# IF.net
KiCad netlist of a schematic drawn in Altium Designer
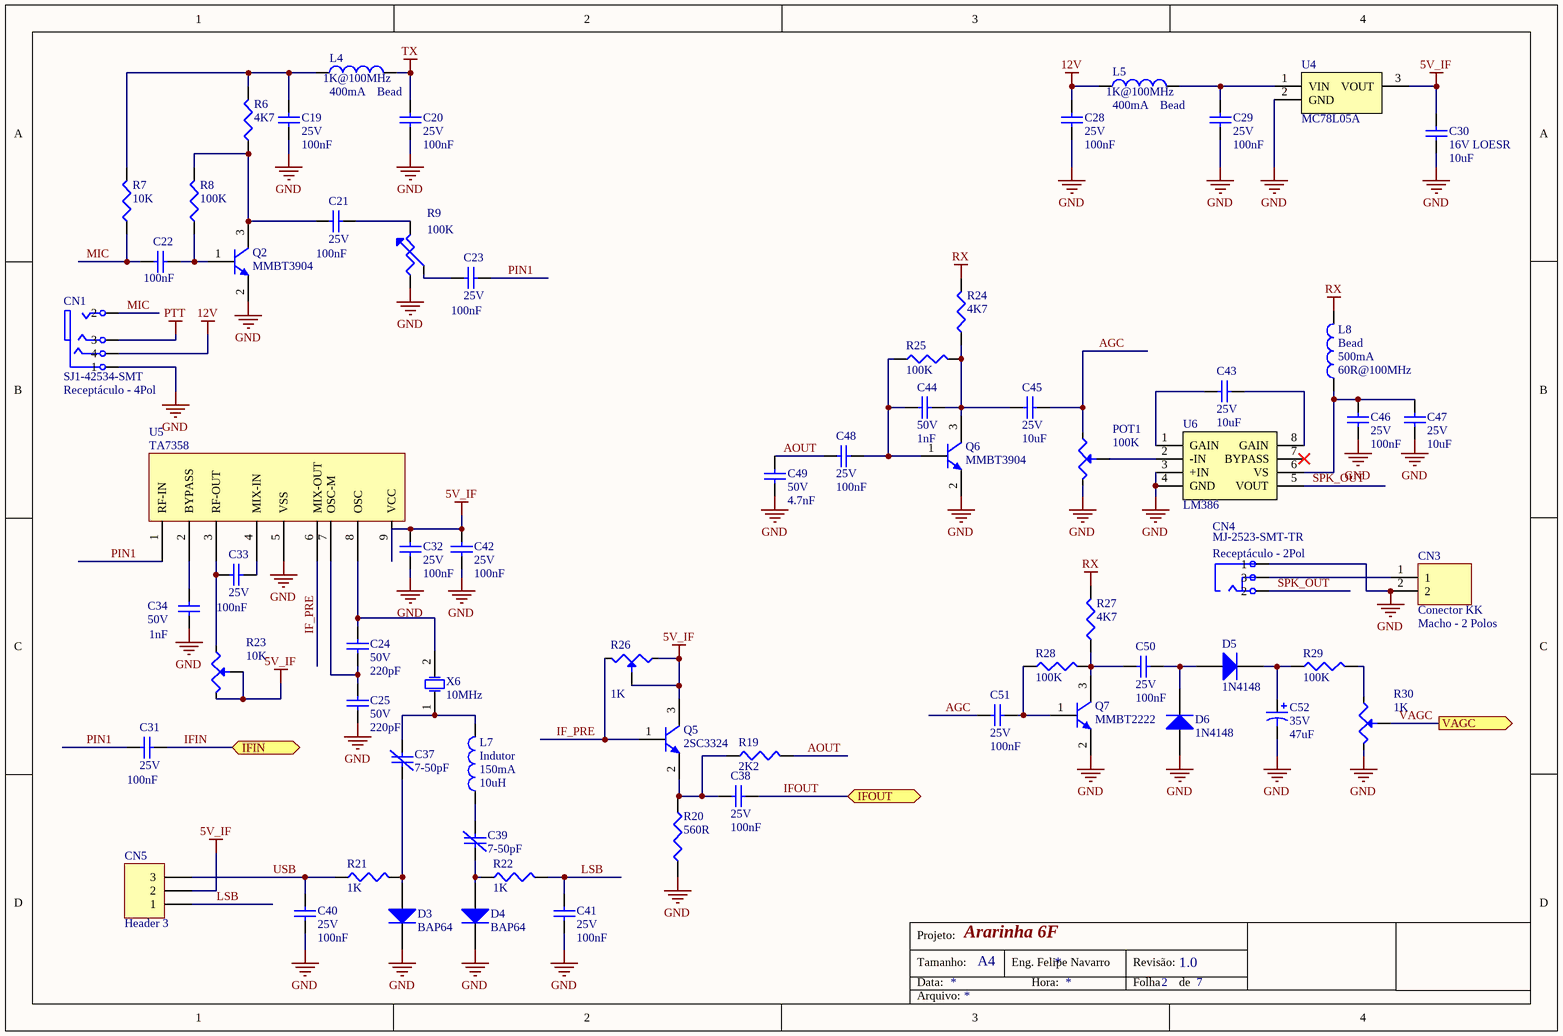
[diagram p0: IF.SchDoc]

(export (version "E")
  (design (tool "Eeschema 10.0.6"))
  (components
    (comp (ref "C19")
      (value "100nF")
      (footprint "CC0603")
      (description "Capacitor (Semiconductor SIM Model)")
      (fields (field (name "TENSÃO") "25V") (field (name "Comment") "Capacitor Cerâmico"))
      (libsource (lib "NavarroCAP") (part "Cap 100nF 25V 0603 X7R"))
    )
    (comp (ref "C20")
      (value "100nF")
      (footprint "CC0603")
      (description "Capacitor (Semiconductor SIM Model)")
      (fields (field (name "TENSÃO") "25V") (field (name "Comment") "Capacitor Cerâmico"))
      (libsource (lib "NavarroCAP") (part "Cap 100nF 25V 0603 X7R"))
    )
    (comp (ref "C21")
      (value "100nF")
      (footprint "CC0603")
      (description "Capacitor (Semiconductor SIM Model)")
      (fields (field (name "TENSÃO") "25V") (field (name "Comment") "Capacitor Cerâmico"))
      (libsource (lib "NavarroCAP") (part "Cap 100nF 25V 0603 X7R"))
    )
    (comp (ref "C22")
      (value "100nF")
      (footprint "CC0603")
      (description "Capacitor (Semiconductor SIM Model)")
      (fields (field (name "Comment") "Capacitor Cerâmico"))
      (libsource (lib "NavarroCAP") (part "Cap 100nF 25V 0603 X7R"))
    )
    (comp (ref "C23")
      (value "100nF")
      (footprint "CC0603")
      (description "Capacitor (Semiconductor SIM Model)")
      (fields (field (name "TENSÃO") "25V") (field (name "Comment") "Capacitor Cerâmico"))
      (libsource (lib "NavarroCAP") (part "Cap 100nF 25V 0603 X7R"))
    )
    (comp (ref "C24")
      (value "220pF")
      (footprint "CC0603")
      (description "Capacitor (Semiconductor SIM Model)")
      (fields (field (name "TENSÃO") "50V") (field (name "Comment") "Capacitor Cerâmico"))
      (libsource (lib "NavarroCAP") (part "Cap 220pF 50V 0603 NP0"))
    )
    (comp (ref "C25")
      (value "220pF")
      (footprint "CC0603")
      (description "Capacitor (Semiconductor SIM Model)")
      (fields (field (name "TENSÃO") "50V") (field (name "Comment") "Capacitor Cerâmico"))
      (libsource (lib "NavarroCAP") (part "Cap 220pF 50V 0603 NP0"))
    )
    (comp (ref "C28")
      (value "100nF")
      (footprint "CC0603")
      (description "Capacitor (Semiconductor SIM Model)")
      (fields (field (name "TENSÃO") "25V") (field (name "Comment") "Capacitor Cerâmico"))
      (libsource (lib "NavarroCAP") (part "Cap 100nF 25V 0603 X7R"))
    )
    (comp (ref "C29")
      (value "100nF")
      (footprint "CC0603")
      (description "Capacitor (Semiconductor SIM Model)")
      (fields (field (name "TENSÃO") "25V") (field (name "Comment") "Capacitor Cerâmico"))
      (libsource (lib "NavarroCAP") (part "Cap 100nF 25V 0603 X7R"))
    )
    (comp (ref "C30")
      (value "10uF")
      (footprint "CC0805")
      (description "Capacitor (Semiconductor SIM Model)")
      (fields (field (name "TENSÃO") "16V LOESR") (field (name "Comment") "Capacitor Cerâmico"))
      (libsource (lib "NavarroCAP") (part "Cap 10uF 16V 0805 X6S LOESR"))
    )
    (comp (ref "C31")
      (value "100nF")
      (footprint "CC0603")
      (description "Capacitor (Semiconductor SIM Model)")
      (fields (field (name "TENSÃO") "25V") (field (name "Comment") "Capacitor Cerâmico"))
      (libsource (lib "NavarroCAP") (part "Cap 100nF 25V 0603 X7R"))
    )
    (comp (ref "C32")
      (value "100nF")
      (footprint "CC0603")
      (description "Capacitor (Semiconductor SIM Model)")
      (fields (field (name "TENSÃO") "25V") (field (name "Comment") "Capacitor Cerâmico"))
      (libsource (lib "NavarroCAP") (part "Cap 100nF 25V 0603 X7R"))
    )
    (comp (ref "C33")
      (value "100nF")
      (footprint "CC0603")
      (description "Capacitor (Semiconductor SIM Model)")
      (fields (field (name "TENSÃO") "25V") (field (name "Comment") "Capacitor Cerâmico"))
      (libsource (lib "NavarroCAP") (part "Cap 100nF 25V 0603 X7R"))
    )
    (comp (ref "C34")
      (value "1nF")
      (footprint "CC0603")
      (description "Capacitor (Semiconductor SIM Model)")
      (fields (field (name "TENSÃO") "50V") (field (name "Comment") "Capacitor Cerâmico"))
      (libsource (lib "NavarroCAP") (part "Cap 1nF 50V 0603 NP0"))
    )
    (comp (ref "C37")
      (value "7-50pF")
      (footprint "MURATA TZB4")
      (description "Capacitor (Semiconductor SIM Model)")
      (fields (field (name "Comment") "Trimmer"))
      (libsource (lib "NavarroCAP") (part "Trimmer 7-50pF 50V TZB4-BB"))
    )
    (comp (ref "C38")
      (value "100nF")
      (footprint "CC0603")
      (description "Capacitor (Semiconductor SIM Model)")
      (fields (field (name "TENSÃO") "25V") (field (name "Comment") "Capacitor Cerâmico"))
      (libsource (lib "NavarroCAP") (part "Cap 100nF 25V 0603 X7R"))
    )
    (comp (ref "C39")
      (value "7-50pF")
      (footprint "MURATA TZB4")
      (description "Capacitor (Semiconductor SIM Model)")
      (fields (field (name "Comment") "Trimmer"))
      (libsource (lib "NavarroCAP") (part "Trimmer 7-50pF 50V TZB4-BB"))
    )
    (comp (ref "C40")
      (value "100nF")
      (footprint "CC0603")
      (description "Capacitor (Semiconductor SIM Model)")
      (fields (field (name "TENSÃO") "25V") (field (name "Comment") "Capacitor Cerâmico"))
      (libsource (lib "NavarroCAP") (part "Cap 100nF 25V 0603 X7R"))
    )
    (comp (ref "C41")
      (value "100nF")
      (footprint "CC0603")
      (description "Capacitor (Semiconductor SIM Model)")
      (fields (field (name "TENSÃO") "25V") (field (name "Comment") "Capacitor Cerâmico"))
      (libsource (lib "NavarroCAP") (part "Cap 100nF 25V 0603 X7R"))
    )
    (comp (ref "C42")
      (value "100nF")
      (footprint "CC0603")
      (description "Capacitor (Semiconductor SIM Model)")
      (fields (field (name "TENSÃO") "25V") (field (name "Comment") "Capacitor Cerâmico"))
      (libsource (lib "NavarroCAP") (part "Cap 100nF 25V 0603 X7R"))
    )
    (comp (ref "C43")
      (value "10uF")
      (footprint "CC0805")
      (description "Capacitor (Semiconductor SIM Model)")
      (fields (field (name "TENSÃO") "25V") (field (name "Comment") "Capacitor Cerâmico"))
      (libsource (lib "NavarroCAP") (part "Cap 10uF 25V 0805 X5R"))
    )
    (comp (ref "C44")
      (value "1nF")
      (footprint "CC0603")
      (description "Capacitor (Semiconductor SIM Model)")
      (fields (field (name "TENSÃO") "50V") (field (name "Comment") "Capacitor Cerâmico"))
      (libsource (lib "NavarroCAP") (part "Cap 1nF 50V 0603 NP0"))
    )
    (comp (ref "C45")
      (value "10uF")
      (footprint "CC0805")
      (description "Capacitor (Semiconductor SIM Model)")
      (fields (field (name "TENSÃO") "25V") (field (name "Comment") "Capacitor Cerâmico"))
      (libsource (lib "NavarroCAP") (part "Cap 10uF 25V 0805 X5R"))
    )
    (comp (ref "C46")
      (value "100nF")
      (footprint "CC0603")
      (description "Capacitor (Semiconductor SIM Model)")
      (fields (field (name "TENSÃO") "25V") (field (name "Comment") "Capacitor Cerâmico"))
      (libsource (lib "NavarroCAP") (part "Cap 100nF 25V 0603 X7R"))
    )
    (comp (ref "C47")
      (value "10uF")
      (footprint "CC0805")
      (description "Capacitor (Semiconductor SIM Model)")
      (fields (field (name "TENSÃO") "25V") (field (name "Comment") "Capacitor Cerâmico"))
      (libsource (lib "NavarroCAP") (part "Cap 10uF 25V 0805 X5R"))
    )
    (comp (ref "C48")
      (value "100nF")
      (footprint "CC0603")
      (description "Capacitor (Semiconductor SIM Model)")
      (fields (field (name "TENSÃO") "25V") (field (name "Comment") "Capacitor Cerâmico"))
      (libsource (lib "NavarroCAP") (part "Cap 100nF 25V 0603 X7R"))
    )
    (comp (ref "C49")
      (value "4.7nF")
      (footprint "CC0603")
      (description "Capacitor (Semiconductor SIM Model)")
      (fields (field (name "TENSÃO") "50V") (field (name "Comment") "Capacitor Cerâmico"))
      (libsource (lib "NavarroCAP") (part "Cap 4.7nF 50V 0603 X7R"))
    )
    (comp (ref "C50")
      (value "100nF")
      (footprint "CC0603")
      (description "Capacitor (Semiconductor SIM Model)")
      (fields (field (name "TENSÃO") "25V") (field (name "Comment") "Capacitor Cerâmico"))
      (libsource (lib "NavarroCAP") (part "Cap 100nF 25V 0603 X7R"))
    )
    (comp (ref "C51")
      (value "100nF")
      (footprint "CC0603")
      (description "Capacitor (Semiconductor SIM Model)")
      (fields (field (name "TENSÃO") "25V") (field (name "Comment") "Capacitor Cerâmico"))
      (libsource (lib "NavarroCAP") (part "Cap 100nF 25V 0603 X7R"))
    )
    (comp (ref "C52")
      (value "47uF")
      (footprint "CPOLRAD5X11")
      (description "Polarized Capacitor (Radial)")
      (fields (field (name "TENSÃO") "35V") (field (name "Comment") "Capacitor Eletrolítico"))
      (libsource (lib "NavarroCAP") (part "PCap 47uF 35V 5d.x11h."))
    )
    (comp (ref "CN1")
      (value "SJ1-42534-SMT")
      (footprint "CONN_JACK-P2_2.5-4N")
      (description "Jack Socket, SMD Vertical, 4-Conductor Open Circuit")
      (fields (field (name "ALTIUM_VALUE") "Receptáculo - 4Pol"))
      (libsource (lib "NavarroCON") (part "Jack-4Pol"))
    )
    (comp (ref "CN3")
      (value "Conector KK")
      (footprint "CONN HDR2-POL P.100")
      (fields (field (name "ALTIUM_VALUE") "Macho - 2 Polos"))
      (libsource (lib "NavarroCON") (part "KK 2P Macho-V P2.54mm"))
    )
    (comp (ref "CN4")
      (value "MJ-2523-SMT-TR")
      (footprint "MJ-2523-SMT-TR")
      (description "CONN AUDIO JACK MONO 2.5MM SMD")
      (fields (field (name "ALTIUM_VALUE") "Receptáculo - 2Pol"))
      (libsource (lib "NavarroCON") (part "MJ-2523-SMT-TR"))
    )
    (comp (ref "CN5")
      (value "Header 3")
      (footprint "CONN HDR1X3")
      (description "Header, 3-Pin")
      (libsource (lib "NavarroCON") (part "Header 3"))
    )
    (comp (ref "D3")
      (value "BAP64")
      (footprint "SOD523")
      (description "PIN DIODE")
      (libsource (lib "NavarroSEMI") (part "PIN BAP64"))
    )
    (comp (ref "D4")
      (value "BAP64")
      (footprint "SOD523")
      (description "PIN DIODE")
      (libsource (lib "NavarroSEMI") (part "PIN BAP64"))
    )
    (comp (ref "D5")
      (value "1N4148")
      (footprint "SOD-323 Diodo-K2")
      (description "Small Signal Diodes")
      (libsource (lib "NavarroSEMI") (part "DP 75V 150mA SOD-323"))
    )
    (comp (ref "D6")
      (value "1N4148")
      (footprint "SOD-323 Diodo-K2")
      (description "Small Signal Diodes")
      (libsource (lib "NavarroSEMI") (part "DP 75V 150mA SOD-323"))
    )
    (comp (ref "L4")
      (value "Bead")
      (footprint "CC0603")
      (fields (field (name "CORRENTE") "400mA") (field (name "ALTIUM_VALUE") "1K@100MHz"))
      (libsource (lib "NavarroIND") (part "Bd 1K@100MHz 0603 400mA"))
    )
    (comp (ref "L5")
      (value "Bead")
      (footprint "CC0603")
      (fields (field (name "CORRENTE") "400mA") (field (name "ALTIUM_VALUE") "1K@100MHz"))
      (libsource (lib "NavarroIND") (part "Bd 1K@100MHz 0603 400mA"))
    )
    (comp (ref "L7")
      (value "Indutor")
      (footprint "CC0805")
      (description "Inductor")
      (fields (field (name "CORRENTE") "150mA") (field (name "ALTIUM_VALUE") "10uH"))
      (libsource (lib "NavarroIND") (part "Ind 10uH 0805 150mA"))
    )
    (comp (ref "L8")
      (value "Bead")
      (footprint "CC0603")
      (fields (field (name "CORRENTE") "500mA") (field (name "ALTIUM_VALUE") "60R@100MHz"))
      (libsource (lib "NavarroIND") (part "Bd 60R@100MHz 0603 500mA"))
    )
    (comp (ref "POT1")
      (value "100K")
      (footprint "POT - PTV09")
      (description "Potenciometro")
      (fields (field (name "Comment") "Potenciômetro"))
      (libsource (lib "NavarroRES") (part "POT 100k Audio"))
    )
    (comp (ref "Q2")
      (value "MMBT3904")
      (footprint "SOT-23-3N")
      (description "NPN General Purpose Amplifier")
      (libsource (lib "NavarroSEMI") (part "TRS MMBT3904 40V 200mA SOT-23-3N"))
    )
    (comp (ref "Q5")
      (value "2SC3324")
      (footprint "SOT-23-3N")
      (description "NPN General Purpose Amplifier")
      (libsource (lib "NavarroSEMI") (part "TRS 2SC3324 120V 100mA SOT-23-3"))
    )
    (comp (ref "Q6")
      (value "MMBT3904")
      (footprint "SOT-23-3N")
      (description "NPN General Purpose Amplifier")
      (libsource (lib "NavarroSEMI") (part "TRS MMBT3904 40V 200mA SOT-23-3N"))
    )
    (comp (ref "Q7")
      (value "MMBT2222")
      (footprint "SOT-23-3N")
      (description "NPN General Purpose Amplifier")
      (libsource (lib "NavarroSEMI") (part "TRS MMBT2222 40V 200mA SOT-23-3N"))
    )
    (comp (ref "R6")
      (value "4K7")
      (footprint "CC0603")
      (description "Resistor")
      (libsource (lib "NavarroRES") (part "Res 4K7 1% 0603 1/10W"))
    )
    (comp (ref "R7")
      (value "10K")
      (footprint "CC0603")
      (description "Resistor")
      (libsource (lib "NavarroRES") (part "Res 10K 1% 0603 1/10W"))
    )
    (comp (ref "R8")
      (value "100K")
      (footprint "CC0603")
      (description "Resistor")
      (libsource (lib "NavarroRES") (part "Res 100K 1% 0603 1/10W"))
    )
    (comp (ref "R9")
      (value "100K")
      (footprint "POT")
      (description "Trimmer")
      (fields (field (name "Comment") "Potenciômetro"))
      (libsource (lib "NavarroRES") (part "Res Trim"))
    )
    (comp (ref "R19")
      (value "2K2")
      (footprint "CC0603")
      (description "Resistor")
      (libsource (lib "NavarroRES") (part "Res 2K2 5% 0603 1/10W"))
    )
    (comp (ref "R20")
      (value "560R")
      (footprint "CC0603")
      (description "Resistor")
      (libsource (lib "NavarroRES") (part "Res 560R 1% 0603 1/10w"))
    )
    (comp (ref "R21")
      (value "1K")
      (footprint "CC0603")
      (description "Resistor")
      (libsource (lib "NavarroRES") (part "Res 1K 1% 0603 1/10W"))
    )
    (comp (ref "R22")
      (value "1K")
      (footprint "CC0603")
      (description "Resistor")
      (libsource (lib "NavarroRES") (part "Res 1K 1% 0603 1/10W"))
    )
    (comp (ref "R23")
      (value "10K")
      (footprint "POT")
      (description "Potenciometro")
      (fields (field (name "Comment") "Potenciômetro"))
      (libsource (lib "NavarroRES") (part "Res Pot"))
    )
    (comp (ref "R24")
      (value "4K7")
      (footprint "CC0603")
      (description "Resistor")
      (libsource (lib "NavarroRES") (part "Res 4K7 1% 0603 1/10W"))
    )
    (comp (ref "R25")
      (value "100K")
      (footprint "CC0603")
      (description "Resistor")
      (libsource (lib "NavarroRES") (part "Res 100K 1% 0603 1/10W"))
    )
    (comp (ref "R26")
      (value "1K")
      (footprint "POT")
      (description "Potenciometro")
      (fields (field (name "Comment") "Potenciômetro"))
      (libsource (lib "NavarroRES") (part "Res Pot"))
    )
    (comp (ref "R27")
      (value "4K7")
      (footprint "CC0603")
      (description "Resistor")
      (libsource (lib "NavarroRES") (part "Res 4K7 1% 0603 1/10W"))
    )
    (comp (ref "R28")
      (value "100K")
      (footprint "CC0603")
      (description "Resistor")
      (libsource (lib "NavarroRES") (part "Res 100K 1% 0603 1/10W"))
    )
    (comp (ref "R29")
      (value "100K")
      (footprint "CC0603")
      (description "Resistor")
      (libsource (lib "NavarroRES") (part "Res 100K 1% 0603 1/10W"))
    )
    (comp (ref "R30")
      (value "1K")
      (footprint "POT")
      (description "Potenciometro")
      (fields (field (name "Comment") "Potenciômetro"))
      (libsource (lib "NavarroRES") (part "Res Pot"))
    )
    (comp (ref "U4")
      (value "MC78L05A")
      (footprint "SOT-89-3N")
      (description "Regulador Linear 5V")
      (libsource (lib "Navarro") (part "MC78L05"))
    )
    (comp (ref "U5")
      (value "TA7358")
      (footprint "SIP9")
      (description "FM FRONT-END")
      (libsource (lib "Navarro") (part "TA7358"))
    )
    (comp (ref "U6")
      (value "LM386")
      (footprint "SOIC-8N")
      (description "IC AMP AUDIO PWR .325W AB 8SOIC")
      (libsource (lib "Navarro") (part "LM386"))
    )
    (comp (ref "X6")
      (value "10MHz")
      (footprint "HC/49US")
      (description "Crystal Oscillator")
      (libsource (lib "Navarro") (part "XTAL"))
    )
  )
  (nets
    (net (code "1") (name "/AGC") (class "Default")
      (node (ref "C45") (pin "2") (pinfunction "2_2") (pintype "passive"))
      (node (ref "C51") (pin "1") (pinfunction "1_1") (pintype "passive"))
      (node (ref "POT1") (pin "1") (pinfunction "1_1") (pintype "passive"))
    )
    (net (code "2") (name "/AOUT") (class "Default")
      (node (ref "C48") (pin "1") (pinfunction "1_1") (pintype "passive"))
      (node (ref "C49") (pin "2") (pinfunction "2_2") (pintype "passive"))
      (node (ref "R19") (pin "2") (pinfunction "2_2") (pintype "passive"))
    )
    (net (code "3") (name "/IFIN") (class "Default")
      (node (ref "C31") (pin "1") (pinfunction "1_1") (pintype "passive"))
    )
    (net (code "4") (name "/IFOUT") (class "Default")
      (node (ref "C38") (pin "2") (pinfunction "2_2") (pintype "passive"))
    )
    (net (code "5") (name "/IF_PRE") (class "Default")
      (node (ref "Q5") (pin "1") (pinfunction "B_1") (pintype "passive"))
      (node (ref "R26") (pin "3") (pinfunction "3_3") (pintype "passive"))
      (node (ref "U5") (pin "6") (pinfunction "MIX-OUT_6") (pintype "passive"))
    )
    (net (code "6") (name "/LSB") (class "Default")
      (node (ref "C41") (pin "1") (pinfunction "1_1") (pintype "passive"))
      (node (ref "CN5") (pin "1") (pinfunction "1_1") (pintype "passive"))
      (node (ref "R22") (pin "2") (pinfunction "2_2") (pintype "passive"))
    )
    (net (code "7") (name "/MIC") (class "Default")
      (node (ref "C22") (pin "2") (pinfunction "2_2") (pintype "passive"))
      (node (ref "CN1") (pin "2") (pinfunction "2_2") (pintype "power_in"))
      (node (ref "R7") (pin "1") (pinfunction "1_1") (pintype "passive"))
    )
    (net (code "8") (name "/PIN1") (class "Default")
      (node (ref "C23") (pin "1") (pinfunction "1_1") (pintype "passive"))
      (node (ref "C31") (pin "2") (pinfunction "2_2") (pintype "passive"))
      (node (ref "U5") (pin "1") (pinfunction "RF-IN_1") (pintype "passive"))
    )
    (net (code "9") (name "/SPK_OUT") (class "Default")
      (node (ref "CN4") (pin "2") (pinfunction "2_2") (pintype "power_in"))
      (node (ref "U6") (pin "5") (pinfunction "VOUT_5") (pintype "passive"))
    )
    (net (code "10") (name "/USB") (class "Default")
      (node (ref "C40") (pin "1") (pinfunction "1_1") (pintype "passive"))
      (node (ref "CN5") (pin "3") (pinfunction "3_3") (pintype "passive"))
      (node (ref "R21") (pin "1") (pinfunction "1_1") (pintype "passive"))
    )
    (net (code "11") (name "/VAGC") (class "Default")
      (node (ref "R30") (pin "2") (pinfunction "TAP_2") (pintype "passive"))
    )
    (net (code "12") (name "5V_IF") (class "Default")
      (node (ref "C30") (pin "2") (pinfunction "2_2") (pintype "passive"))
      (node (ref "C32") (pin "1") (pinfunction "1_1") (pintype "passive"))
      (node (ref "C42") (pin "1") (pinfunction "1_1") (pintype "passive"))
      (node (ref "CN5") (pin "2") (pinfunction "2_2") (pintype "passive"))
      (node (ref "Q5") (pin "3") (pinfunction "C_3") (pintype "passive"))
      (node (ref "R23") (pin "2") (pinfunction "TAP_2") (pintype "passive"))
      (node (ref "R23") (pin "3") (pinfunction "3_3") (pintype "passive"))
      (node (ref "R26") (pin "1") (pinfunction "1_1") (pintype "passive"))
      (node (ref "R26") (pin "2") (pinfunction "TAP_2") (pintype "passive"))
      (node (ref "U4") (pin "3") (pinfunction "VOUT_3") (pintype "power_in"))
      (node (ref "U5") (pin "9") (pinfunction "VCC_9") (pintype "passive"))
    )
    (net (code "13") (name "12V") (class "Default")
      (node (ref "C28") (pin "1") (pinfunction "1_1") (pintype "passive"))
      (node (ref "CN1") (pin "4") (pinfunction "4_4") (pintype "power_in"))
      (node (ref "L5") (pin "1") (pinfunction "1_1") (pintype "passive"))
    )
    (net (code "14") (name "GND") (class "Default")
      (node (ref "C19") (pin "2") (pinfunction "2_2") (pintype "passive"))
      (node (ref "C20") (pin "2") (pinfunction "2_2") (pintype "passive"))
      (node (ref "C25") (pin "1") (pinfunction "1_1") (pintype "passive"))
      (node (ref "C28") (pin "2") (pinfunction "2_2") (pintype "passive"))
      (node (ref "C29") (pin "2") (pinfunction "2_2") (pintype "passive"))
      (node (ref "C30") (pin "1") (pinfunction "1_1") (pintype "passive"))
      (node (ref "C32") (pin "2") (pinfunction "2_2") (pintype "passive"))
      (node (ref "C34") (pin "2") (pinfunction "2_2") (pintype "passive"))
      (node (ref "C40") (pin "2") (pinfunction "2_2") (pintype "passive"))
      (node (ref "C41") (pin "2") (pinfunction "2_2") (pintype "passive"))
      (node (ref "C42") (pin "2") (pinfunction "2_2") (pintype "passive"))
      (node (ref "C46") (pin "2") (pinfunction "2_2") (pintype "passive"))
      (node (ref "C47") (pin "1") (pinfunction "1_1") (pintype "passive"))
      (node (ref "C49") (pin "1") (pinfunction "1_1") (pintype "passive"))
      (node (ref "C52") (pin "2") (pinfunction "2_2") (pintype "passive"))
      (node (ref "CN1") (pin "1") (pinfunction "1_1") (pintype "passive"))
      (node (ref "CN3") (pin "2") (pinfunction "2_2") (pintype "passive"))
      (node (ref "CN4") (pin "1") (pinfunction "1_1") (pintype "passive"))
      (node (ref "D3") (pin "2") (pinfunction "K_2") (pintype "passive"))
      (node (ref "D4") (pin "2") (pinfunction "K_2") (pintype "passive"))
      (node (ref "D6") (pin "1") (pinfunction "A_1") (pintype "passive"))
      (node (ref "POT1") (pin "3") (pinfunction "3_3") (pintype "passive"))
      (node (ref "Q2") (pin "2") (pinfunction "E_2") (pintype "passive"))
      (node (ref "Q6") (pin "2") (pinfunction "E_2") (pintype "passive"))
      (node (ref "Q7") (pin "2") (pinfunction "E_2") (pintype "passive"))
      (node (ref "R20") (pin "1") (pinfunction "1_1") (pintype "passive"))
      (node (ref "R30") (pin "3") (pinfunction "3_3") (pintype "passive"))
      (node (ref "R9") (pin "2") (pinfunction "2_2") (pintype "passive"))
      (node (ref "U4") (pin "2") (pinfunction "GND_2") (pintype "power_in"))
      (node (ref "U5") (pin "5") (pinfunction "VSS_5") (pintype "passive"))
      (node (ref "U6") (pin "3") (pinfunction "+IN_3") (pintype "passive"))
      (node (ref "U6") (pin "4") (pinfunction "GND_4") (pintype "passive"))
    )
    (net (code "15") (name "Net-(C19-Pad1)") (class "Default")
      (node (ref "C19") (pin "1") (pinfunction "1_1") (pintype "passive"))
      (node (ref "L4") (pin "1") (pinfunction "1_1") (pintype "passive"))
      (node (ref "R6") (pin "2") (pinfunction "2_2") (pintype "passive"))
      (node (ref "R7") (pin "2") (pinfunction "2_2") (pintype "passive"))
    )
    (net (code "16") (name "Net-(C21-Pad1)") (class "Default")
      (node (ref "C21") (pin "1") (pinfunction "1_1") (pintype "passive"))
      (node (ref "R9") (pin "1") (pinfunction "1_1") (pintype "passive"))
    )
    (net (code "17") (name "Net-(C39-Pad2)") (class "Default")
      (node (ref "C39") (pin "2") (pinfunction "2_2") (pintype "passive"))
      (node (ref "L7") (pin "1") (pinfunction "1_1") (pintype "passive"))
    )
    (net (code "18") (name "Net-(C43-Pad1)") (class "Default")
      (node (ref "C43") (pin "1") (pinfunction "1_1") (pintype "passive"))
      (node (ref "U6") (pin "1") (pinfunction "GAIN_1") (pintype "passive"))
    )
    (net (code "19") (name "Net-(C43-Pad2)") (class "Default")
      (node (ref "C43") (pin "2") (pinfunction "2_2") (pintype "passive"))
      (node (ref "U6") (pin "8") (pinfunction "GAIN_8") (pintype "passive"))
    )
    (net (code "20") (name "Net-(CN3-Pad1)") (class "Default")
      (node (ref "CN3") (pin "1") (pinfunction "1_1") (pintype "passive"))
      (node (ref "CN4") (pin "3") (pinfunction "3_3") (pintype "power_in"))
    )
    (net (code "21") (name "Net-(D3-A)") (class "Default")
      (node (ref "C37") (pin "1") (pinfunction "1_1") (pintype "passive"))
      (node (ref "D3") (pin "1") (pinfunction "A_1") (pintype "passive"))
      (node (ref "R21") (pin "2") (pinfunction "2_2") (pintype "passive"))
    )
    (net (code "22") (name "Net-(D4-A)") (class "Default")
      (node (ref "C39") (pin "1") (pinfunction "1_1") (pintype "passive"))
      (node (ref "D4") (pin "1") (pinfunction "A_1") (pintype "passive"))
      (node (ref "R22") (pin "1") (pinfunction "1_1") (pintype "passive"))
    )
    (net (code "23") (name "Net-(D5-A)") (class "Default")
      (node (ref "C50") (pin "2") (pinfunction "2_2") (pintype "passive"))
      (node (ref "D5") (pin "1") (pinfunction "A_1") (pintype "passive"))
      (node (ref "D6") (pin "2") (pinfunction "K_2") (pintype "passive"))
    )
    (net (code "24") (name "Net-(D5-K)") (class "Default")
      (node (ref "C52") (pin "1") (pinfunction "1_1") (pintype "passive"))
      (node (ref "D5") (pin "2") (pinfunction "K_2") (pintype "passive"))
      (node (ref "R29") (pin "1") (pinfunction "1_1") (pintype "passive"))
    )
    (net (code "25") (name "Net-(POT1-TAP)") (class "Default")
      (node (ref "POT1") (pin "2") (pinfunction "TAP_2") (pintype "passive"))
      (node (ref "U6") (pin "2") (pinfunction "-IN_2") (pintype "passive"))
    )
    (net (code "26") (name "Net-(Q2-B)") (class "Default")
      (node (ref "C22") (pin "1") (pinfunction "1_1") (pintype "passive"))
      (node (ref "Q2") (pin "1") (pinfunction "B_1") (pintype "passive"))
      (node (ref "R8") (pin "1") (pinfunction "1_1") (pintype "passive"))
    )
    (net (code "27") (name "Net-(Q2-C)") (class "Default")
      (node (ref "C21") (pin "2") (pinfunction "2_2") (pintype "passive"))
      (node (ref "Q2") (pin "3") (pinfunction "C_3") (pintype "passive"))
      (node (ref "R6") (pin "1") (pinfunction "1_1") (pintype "passive"))
      (node (ref "R8") (pin "2") (pinfunction "2_2") (pintype "passive"))
    )
    (net (code "28") (name "Net-(Q5-E)") (class "Default")
      (node (ref "C38") (pin "1") (pinfunction "1_1") (pintype "passive"))
      (node (ref "Q5") (pin "2") (pinfunction "E_2") (pintype "passive"))
      (node (ref "R19") (pin "1") (pinfunction "1_1") (pintype "passive"))
      (node (ref "R20") (pin "2") (pinfunction "2_2") (pintype "passive"))
    )
    (net (code "29") (name "Net-(Q6-B)") (class "Default")
      (node (ref "C44") (pin "1") (pinfunction "1_1") (pintype "passive"))
      (node (ref "C48") (pin "2") (pinfunction "2_2") (pintype "passive"))
      (node (ref "Q6") (pin "1") (pinfunction "B_1") (pintype "passive"))
      (node (ref "R25") (pin "1") (pinfunction "1_1") (pintype "passive"))
    )
    (net (code "30") (name "Net-(Q6-C)") (class "Default")
      (node (ref "C44") (pin "2") (pinfunction "2_2") (pintype "passive"))
      (node (ref "C45") (pin "1") (pinfunction "1_1") (pintype "passive"))
      (node (ref "Q6") (pin "3") (pinfunction "C_3") (pintype "passive"))
      (node (ref "R24") (pin "1") (pinfunction "1_1") (pintype "passive"))
      (node (ref "R25") (pin "2") (pinfunction "2_2") (pintype "passive"))
    )
    (net (code "31") (name "Net-(Q7-B)") (class "Default")
      (node (ref "C51") (pin "2") (pinfunction "2_2") (pintype "passive"))
      (node (ref "Q7") (pin "1") (pinfunction "B_1") (pintype "passive"))
      (node (ref "R28") (pin "1") (pinfunction "1_1") (pintype "passive"))
    )
    (net (code "32") (name "Net-(Q7-C)") (class "Default")
      (node (ref "C50") (pin "1") (pinfunction "1_1") (pintype "passive"))
      (node (ref "Q7") (pin "3") (pinfunction "C_3") (pintype "passive"))
      (node (ref "R27") (pin "1") (pinfunction "1_1") (pintype "passive"))
      (node (ref "R28") (pin "2") (pinfunction "2_2") (pintype "passive"))
    )
    (net (code "33") (name "Net-(R9-TAP)") (class "Default")
      (node (ref "C23") (pin "2") (pinfunction "2_2") (pintype "passive"))
      (node (ref "R9") (pin "3") (pinfunction "TAP_3") (pintype "passive"))
    )
    (net (code "34") (name "Net-(R29-Pad2)") (class "Default")
      (node (ref "R29") (pin "2") (pinfunction "2_2") (pintype "passive"))
      (node (ref "R30") (pin "1") (pinfunction "1_1") (pintype "passive"))
    )
    (net (code "35") (name "Net-(U4-VIN)") (class "Default")
      (node (ref "C29") (pin "1") (pinfunction "1_1") (pintype "passive"))
      (node (ref "L5") (pin "2") (pinfunction "2_2") (pintype "passive"))
      (node (ref "U4") (pin "1") (pinfunction "VIN_1") (pintype "power_in"))
    )
    (net (code "36") (name "Net-(U5-BYPASS)") (class "Default")
      (node (ref "C34") (pin "1") (pinfunction "1_1") (pintype "passive"))
      (node (ref "U5") (pin "2") (pinfunction "BYPASS_2") (pintype "passive"))
    )
    (net (code "37") (name "Net-(U5-MIX-IN)") (class "Default")
      (node (ref "C33") (pin "1") (pinfunction "1_1") (pintype "passive"))
      (node (ref "U5") (pin "4") (pinfunction "MIX-IN_4") (pintype "passive"))
    )
    (net (code "38") (name "Net-(U5-OSC)") (class "Default")
      (node (ref "C24") (pin "2") (pinfunction "2_2") (pintype "passive"))
      (node (ref "U5") (pin "8") (pinfunction "OSC_8") (pintype "passive"))
      (node (ref "X6") (pin "2") (pinfunction "OSC2_2") (pintype "passive"))
    )
    (net (code "39") (name "Net-(U5-OSC-M)") (class "Default")
      (node (ref "C24") (pin "1") (pinfunction "1_1") (pintype "passive"))
      (node (ref "C25") (pin "2") (pinfunction "2_2") (pintype "passive"))
      (node (ref "U5") (pin "7") (pinfunction "OSC-M_7") (pintype "passive"))
    )
    (net (code "40") (name "Net-(U5-RF-OUT)") (class "Default")
      (node (ref "C33") (pin "2") (pinfunction "2_2") (pintype "passive"))
      (node (ref "R23") (pin "1") (pinfunction "1_1") (pintype "passive"))
      (node (ref "U5") (pin "3") (pinfunction "RF-OUT_3") (pintype "passive"))
    )
    (net (code "41") (name "Net-(U6-VS)") (class "Default")
      (node (ref "C46") (pin "1") (pinfunction "1_1") (pintype "passive"))
      (node (ref "C47") (pin "2") (pinfunction "2_2") (pintype "passive"))
      (node (ref "L8") (pin "1") (pinfunction "1_1") (pintype "passive"))
      (node (ref "U6") (pin "6") (pinfunction "VS_6") (pintype "passive"))
    )
    (net (code "42") (name "Net-(X6-OSC1)") (class "Default")
      (node (ref "C37") (pin "2") (pinfunction "2_2") (pintype "passive"))
      (node (ref "L7") (pin "2") (pinfunction "2_2") (pintype "passive"))
      (node (ref "X6") (pin "1") (pinfunction "OSC1_1") (pintype "passive"))
    )
    (net (code "43") (name "PTT") (class "Default")
      (node (ref "CN1") (pin "3") (pinfunction "3_3") (pintype "power_in"))
    )
    (net (code "44") (name "RX") (class "Default")
      (node (ref "L8") (pin "2") (pinfunction "2_2") (pintype "passive"))
      (node (ref "R24") (pin "2") (pinfunction "2_2") (pintype "passive"))
      (node (ref "R27") (pin "2") (pinfunction "2_2") (pintype "passive"))
    )
    (net (code "45") (name "TX") (class "Default")
      (node (ref "C20") (pin "1") (pinfunction "1_1") (pintype "passive"))
      (node (ref "L4") (pin "2") (pinfunction "2_2") (pintype "passive"))
    )
    (net (code "46") (name "unconnected-(U6-BYPASS-Pad7)") (class "Default")
      (node (ref "U6") (pin "7") (pinfunction "BYPASS_7") (pintype "passive+no_connect"))
    )
  )
)
